# Digital_Output_CPU.net
KiCad netlist of a schematic drawn in Altium Designer
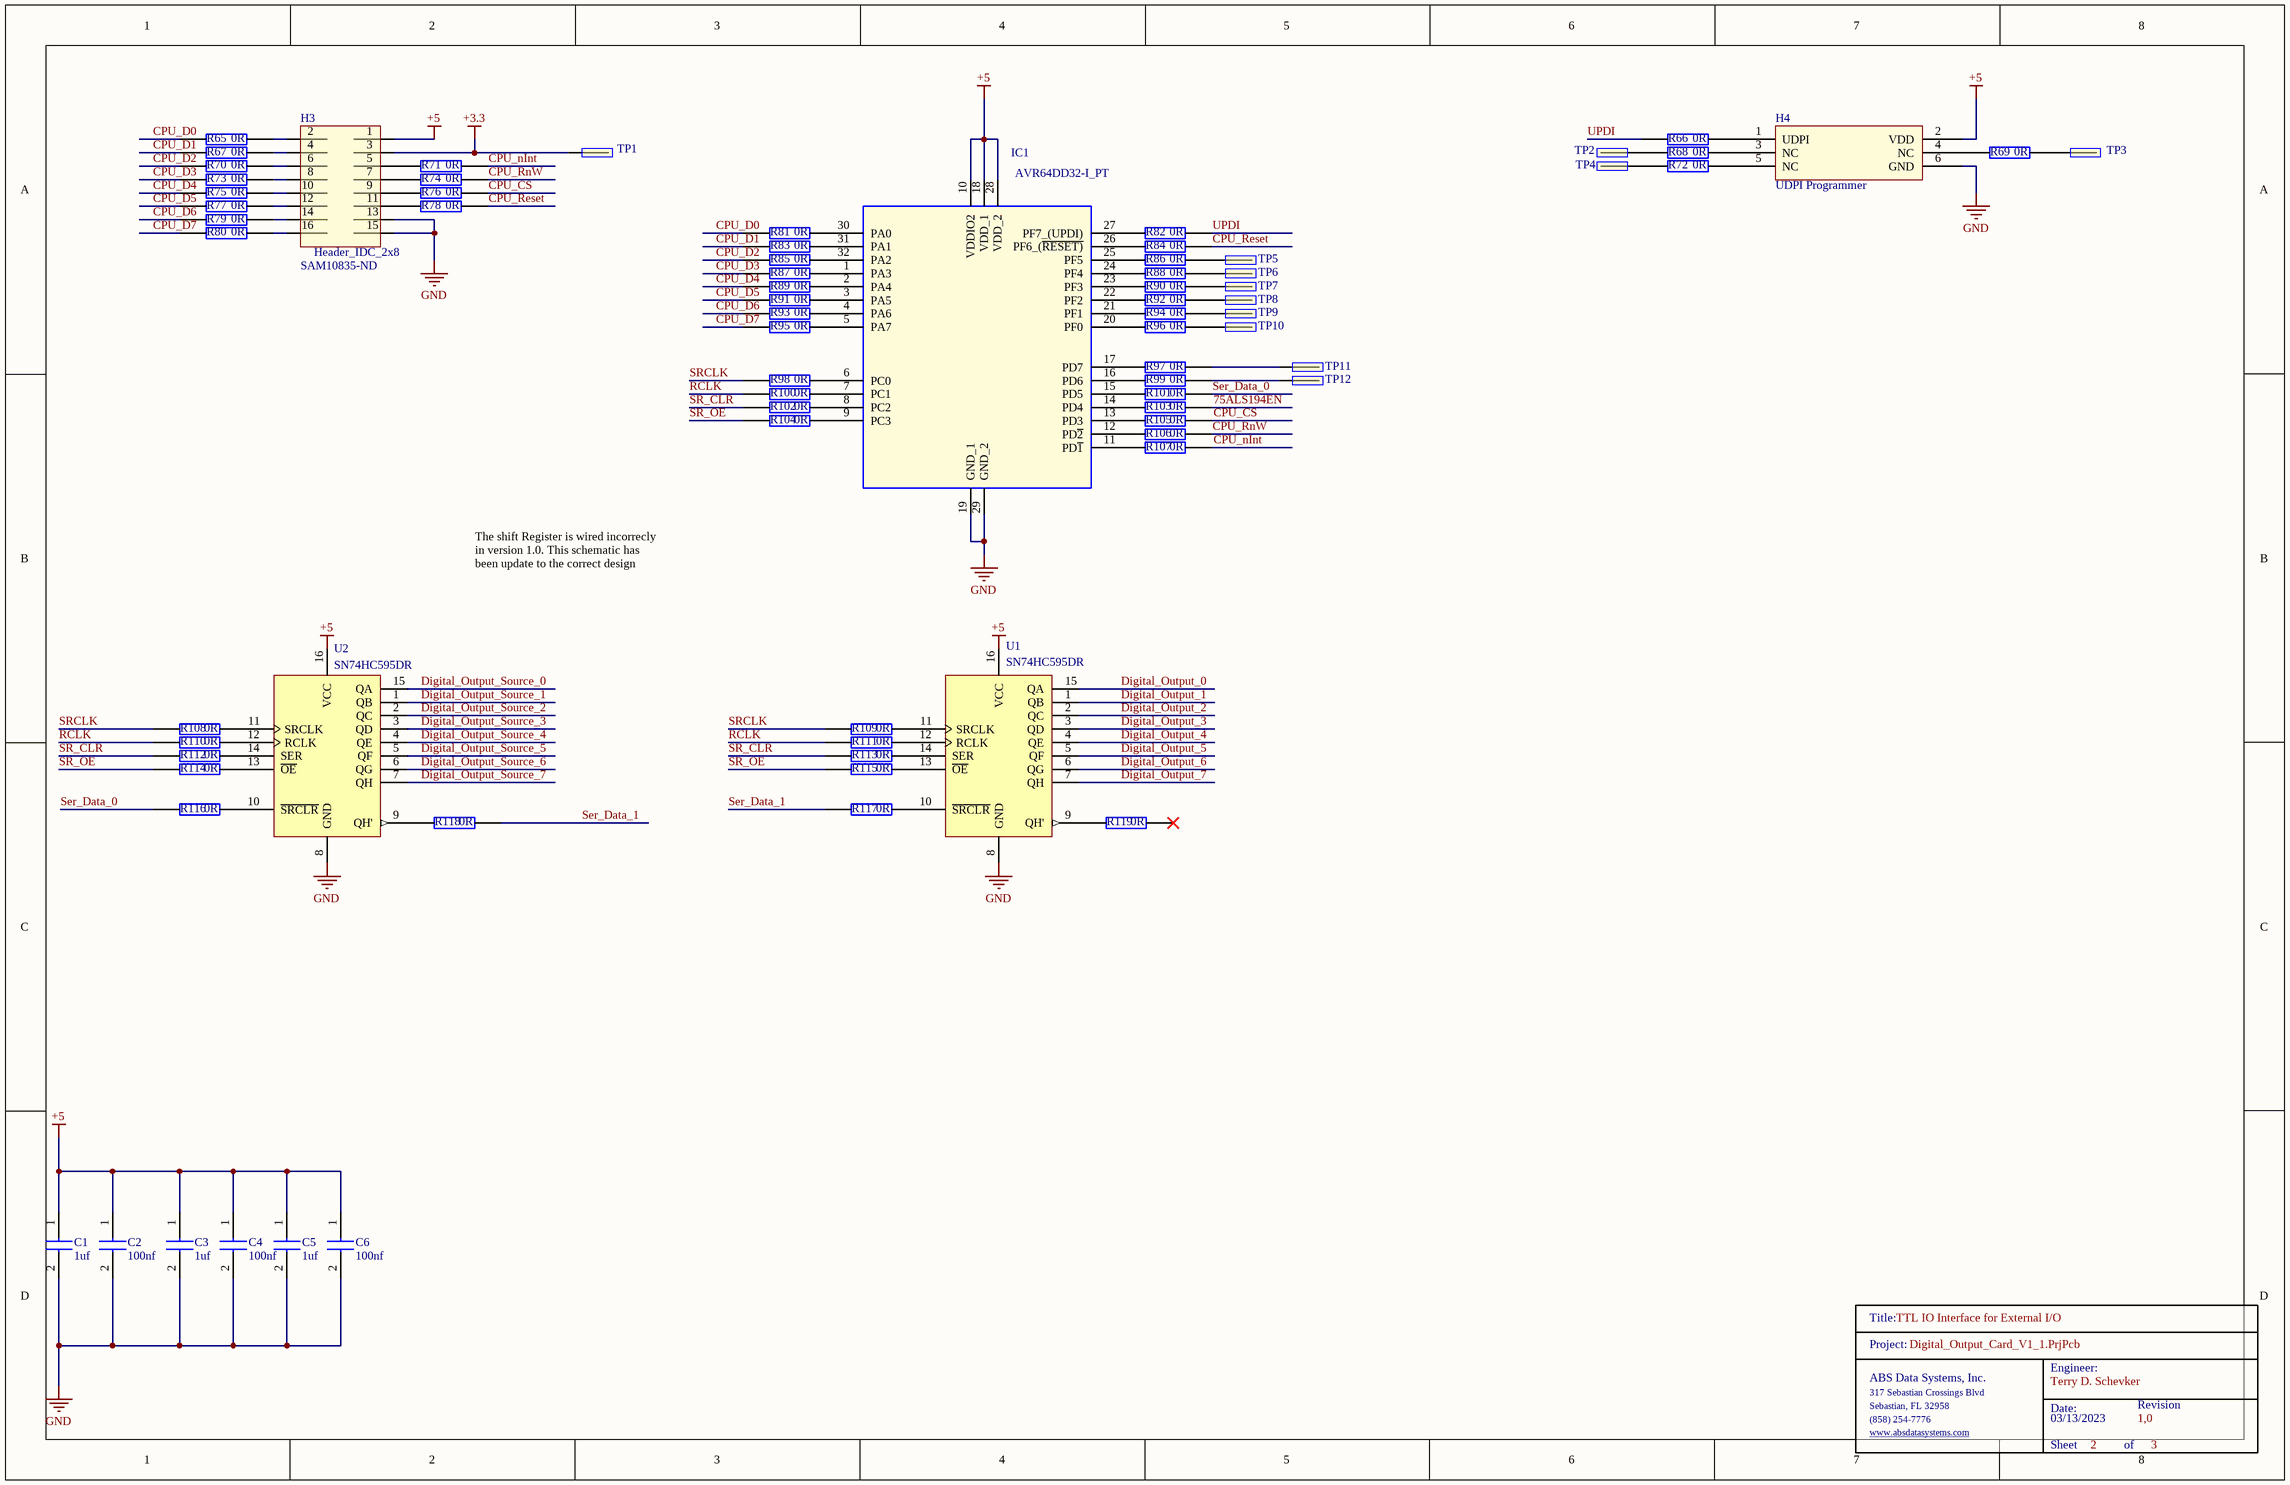
[diagram p0: Digital_Output_CPU.SchDoc]

(export (version "E")
  (design (tool "Eeschema 10.0.6"))
  (components
    (comp (ref "C1")
      (value "1uf")
      (footprint "0603")
      (description "Samsung Electro-Mechanics 0603 1uf")
      (libsource (lib "Capacitors") (part "CL10B105KA8NNNL"))
    )
    (comp (ref "C2")
      (value "100nf")
      (footprint "0603")
      (description "Samsung Electro-Mechanics 0603 100nf")
      (libsource (lib "Capacitors") (part "CL10B104JB8NNNC"))
    )
    (comp (ref "C3")
      (value "1uf")
      (footprint "0603")
      (description "Samsung Electro-Mechanics 0603 1uf")
      (libsource (lib "Capacitors") (part "CL10B105KA8NNNL"))
    )
    (comp (ref "C4")
      (value "100nf")
      (footprint "0603")
      (description "Samsung Electro-Mechanics 0603 100nf")
      (libsource (lib "Capacitors") (part "CL10B104JB8NNNC"))
    )
    (comp (ref "C5")
      (value "1uf")
      (footprint "0603")
      (description "Samsung Electro-Mechanics 0603 1uf")
      (libsource (lib "Capacitors") (part "CL10B105KA8NNNL"))
    )
    (comp (ref "C6")
      (value "100nf")
      (footprint "0603")
      (description "Samsung Electro-Mechanics 0603 100nf")
      (libsource (lib "Capacitors") (part "CL10B104JB8NNNC"))
    )
    (comp (ref "H3")
      (value "Header_IDC_2x8")
      (footprint "HEADER16")
      (description "16 Pin 2x8 Through Hold IDC Connector")
      (fields
        (field (name "MANUFACTURER") "Samtec")
        (field (name "MANUFACTURER PART NUMBER") "TST-108-01-G-D")
        (field (name "SUPPLIER PART NUMBER 1") "SAM10835-ND")
      )
      (libsource (lib "Misc") (part "Header_IDC_2x8"))
    )
    (comp (ref "H4")
      (value "UDPI Programmer")
      (footprint "HDR2X3")
      (description "6 Pin 2X3 Through Hole Header")
      (libsource (lib "Misc") (part "UDPI Programmer"))
    )
    (comp (ref "IC1")
      (value "AVR64DD32-I_PT")
      (footprint "QFP80P900X900X120-32N")
      (description "Integrated Circuit")
      (fields (field (name "MANUFACTURER_PART_NUMBER") "AVR64DD32-I/PT ¦ MULTI-VOLTAGE I/O"))
      (libsource (lib "CPU_Memory") (part "AVR64DD32-I_PT"))
    )
    (comp (ref "R65")
      (value "0R")
      (footprint "0603")
      (description "YAGEO 0603 0 ohm")
      (fields
        (field (name "MOUSER PART NUMBER") "603-RC0603JR-070RL")
        (field (name "MANUFACTURER_PART_NUMBER") "RC0603JR-070RL")
      )
      (libsource (lib "Resistors") (part "RC0603JR-070RL"))
    )
    (comp (ref "R66")
      (value "0R")
      (footprint "0603")
      (description "YAGEO 0603 0 ohm")
      (fields
        (field (name "MOUSER PART NUMBER") "603-RC0603JR-070RL")
        (field (name "MANUFACTURER_PART_NUMBER") "RC0603JR-070RL")
      )
      (libsource (lib "Resistors") (part "RC0603JR-070RL"))
    )
    (comp (ref "R67")
      (value "0R")
      (footprint "0603")
      (description "YAGEO 0603 0 ohm")
      (fields
        (field (name "MOUSER PART NUMBER") "603-RC0603JR-070RL")
        (field (name "MANUFACTURER_PART_NUMBER") "RC0603JR-070RL")
      )
      (libsource (lib "Resistors") (part "RC0603JR-070RL"))
    )
    (comp (ref "R68")
      (value "0R")
      (footprint "0603")
      (description "YAGEO 0603 0 ohm")
      (fields
        (field (name "MOUSER PART NUMBER") "603-RC0603JR-070RL")
        (field (name "MANUFACTURER_PART_NUMBER") "RC0603JR-070RL")
      )
      (libsource (lib "Resistors") (part "RC0603JR-070RL"))
    )
    (comp (ref "R69")
      (value "0R")
      (footprint "0603")
      (description "YAGEO 0603 0 ohm")
      (fields
        (field (name "MOUSER PART NUMBER") "603-RC0603JR-070RL")
        (field (name "MANUFACTURER_PART_NUMBER") "RC0603JR-070RL")
      )
      (libsource (lib "Resistors") (part "RC0603JR-070RL"))
    )
    (comp (ref "R70")
      (value "0R")
      (footprint "0603")
      (description "YAGEO 0603 0 ohm")
      (fields
        (field (name "MOUSER PART NUMBER") "603-RC0603JR-070RL")
        (field (name "MANUFACTURER_PART_NUMBER") "RC0603JR-070RL")
      )
      (libsource (lib "Resistors") (part "RC0603JR-070RL"))
    )
    (comp (ref "R71")
      (value "0R")
      (footprint "0603")
      (description "YAGEO 0603 0 ohm")
      (fields
        (field (name "MOUSER PART NUMBER") "603-RC0603JR-070RL")
        (field (name "MANUFACTURER_PART_NUMBER") "RC0603JR-070RL")
      )
      (libsource (lib "Resistors") (part "RC0603JR-070RL"))
    )
    (comp (ref "R72")
      (value "0R")
      (footprint "0603")
      (description "YAGEO 0603 0 ohm")
      (fields
        (field (name "MOUSER PART NUMBER") "603-RC0603JR-070RL")
        (field (name "MANUFACTURER_PART_NUMBER") "RC0603JR-070RL")
      )
      (libsource (lib "Resistors") (part "RC0603JR-070RL"))
    )
    (comp (ref "R73")
      (value "0R")
      (footprint "0603")
      (description "YAGEO 0603 0 ohm")
      (fields
        (field (name "MOUSER PART NUMBER") "603-RC0603JR-070RL")
        (field (name "MANUFACTURER_PART_NUMBER") "RC0603JR-070RL")
      )
      (libsource (lib "Resistors") (part "RC0603JR-070RL"))
    )
    (comp (ref "R74")
      (value "0R")
      (footprint "0603")
      (description "YAGEO 0603 0 ohm")
      (fields
        (field (name "MOUSER PART NUMBER") "603-RC0603JR-070RL")
        (field (name "MANUFACTURER_PART_NUMBER") "RC0603JR-070RL")
      )
      (libsource (lib "Resistors") (part "RC0603JR-070RL"))
    )
    (comp (ref "R75")
      (value "0R")
      (footprint "0603")
      (description "YAGEO 0603 0 ohm")
      (fields
        (field (name "MOUSER PART NUMBER") "603-RC0603JR-070RL")
        (field (name "MANUFACTURER_PART_NUMBER") "RC0603JR-070RL")
      )
      (libsource (lib "Resistors") (part "RC0603JR-070RL"))
    )
    (comp (ref "R76")
      (value "0R")
      (footprint "0603")
      (description "YAGEO 0603 0 ohm")
      (fields
        (field (name "MOUSER PART NUMBER") "603-RC0603JR-070RL")
        (field (name "MANUFACTURER_PART_NUMBER") "RC0603JR-070RL")
      )
      (libsource (lib "Resistors") (part "RC0603JR-070RL"))
    )
    (comp (ref "R77")
      (value "0R")
      (footprint "0603")
      (description "YAGEO 0603 0 ohm")
      (fields
        (field (name "MOUSER PART NUMBER") "603-RC0603JR-070RL")
        (field (name "MANUFACTURER_PART_NUMBER") "RC0603JR-070RL")
      )
      (libsource (lib "Resistors") (part "RC0603JR-070RL"))
    )
    (comp (ref "R78")
      (value "0R")
      (footprint "0603")
      (description "YAGEO 0603 0 ohm")
      (fields
        (field (name "MOUSER PART NUMBER") "603-RC0603JR-070RL")
        (field (name "MANUFACTURER_PART_NUMBER") "RC0603JR-070RL")
      )
      (libsource (lib "Resistors") (part "RC0603JR-070RL"))
    )
    (comp (ref "R79")
      (value "0R")
      (footprint "0603")
      (description "YAGEO 0603 0 ohm")
      (fields
        (field (name "MOUSER PART NUMBER") "603-RC0603JR-070RL")
        (field (name "MANUFACTURER_PART_NUMBER") "RC0603JR-070RL")
      )
      (libsource (lib "Resistors") (part "RC0603JR-070RL"))
    )
    (comp (ref "R80")
      (value "0R")
      (footprint "0603")
      (description "YAGEO 0603 0 ohm")
      (fields
        (field (name "MOUSER PART NUMBER") "603-RC0603JR-070RL")
        (field (name "MANUFACTURER_PART_NUMBER") "RC0603JR-070RL")
      )
      (libsource (lib "Resistors") (part "RC0603JR-070RL"))
    )
    (comp (ref "R81")
      (value "0R")
      (footprint "0603")
      (description "YAGEO 0603 0 ohm")
      (fields
        (field (name "MOUSER PART NUMBER") "603-RC0603JR-070RL")
        (field (name "MANUFACTURER_PART_NUMBER") "RC0603JR-070RL")
      )
      (libsource (lib "Resistors") (part "RC0603JR-070RL"))
    )
    (comp (ref "R82")
      (value "0R")
      (footprint "0603")
      (description "YAGEO 0603 0 ohm")
      (fields
        (field (name "MOUSER PART NUMBER") "603-RC0603JR-070RL")
        (field (name "MANUFACTURER_PART_NUMBER") "RC0603JR-070RL")
      )
      (libsource (lib "Resistors") (part "RC0603JR-070RL"))
    )
    (comp (ref "R83")
      (value "0R")
      (footprint "0603")
      (description "YAGEO 0603 0 ohm")
      (fields
        (field (name "MOUSER PART NUMBER") "603-RC0603JR-070RL")
        (field (name "MANUFACTURER_PART_NUMBER") "RC0603JR-070RL")
      )
      (libsource (lib "Resistors") (part "RC0603JR-070RL"))
    )
    (comp (ref "R84")
      (value "0R")
      (footprint "0603")
      (description "YAGEO 0603 0 ohm")
      (fields
        (field (name "MOUSER PART NUMBER") "603-RC0603JR-070RL")
        (field (name "MANUFACTURER_PART_NUMBER") "RC0603JR-070RL")
      )
      (libsource (lib "Resistors") (part "RC0603JR-070RL"))
    )
    (comp (ref "R85")
      (value "0R")
      (footprint "0603")
      (description "YAGEO 0603 0 ohm")
      (fields
        (field (name "MOUSER PART NUMBER") "603-RC0603JR-070RL")
        (field (name "MANUFACTURER_PART_NUMBER") "RC0603JR-070RL")
      )
      (libsource (lib "Resistors") (part "RC0603JR-070RL"))
    )
    (comp (ref "R86")
      (value "0R")
      (footprint "0603")
      (description "YAGEO 0603 0 ohm")
      (fields
        (field (name "MOUSER PART NUMBER") "603-RC0603JR-070RL")
        (field (name "MANUFACTURER_PART_NUMBER") "RC0603JR-070RL")
      )
      (libsource (lib "Resistors") (part "RC0603JR-070RL"))
    )
    (comp (ref "R87")
      (value "0R")
      (footprint "0603")
      (description "YAGEO 0603 0 ohm")
      (fields
        (field (name "MOUSER PART NUMBER") "603-RC0603JR-070RL")
        (field (name "MANUFACTURER_PART_NUMBER") "RC0603JR-070RL")
      )
      (libsource (lib "Resistors") (part "RC0603JR-070RL"))
    )
    (comp (ref "R88")
      (value "0R")
      (footprint "0603")
      (description "YAGEO 0603 0 ohm")
      (fields
        (field (name "MOUSER PART NUMBER") "603-RC0603JR-070RL")
        (field (name "MANUFACTURER_PART_NUMBER") "RC0603JR-070RL")
      )
      (libsource (lib "Resistors") (part "RC0603JR-070RL"))
    )
    (comp (ref "R89")
      (value "0R")
      (footprint "0603")
      (description "YAGEO 0603 0 ohm")
      (fields
        (field (name "MOUSER PART NUMBER") "603-RC0603JR-070RL")
        (field (name "MANUFACTURER_PART_NUMBER") "RC0603JR-070RL")
      )
      (libsource (lib "Resistors") (part "RC0603JR-070RL"))
    )
    (comp (ref "R90")
      (value "0R")
      (footprint "0603")
      (description "YAGEO 0603 0 ohm")
      (fields
        (field (name "MOUSER PART NUMBER") "603-RC0603JR-070RL")
        (field (name "MANUFACTURER_PART_NUMBER") "RC0603JR-070RL")
      )
      (libsource (lib "Resistors") (part "RC0603JR-070RL"))
    )
    (comp (ref "R91")
      (value "0R")
      (footprint "0603")
      (description "YAGEO 0603 0 ohm")
      (fields
        (field (name "MOUSER PART NUMBER") "603-RC0603JR-070RL")
        (field (name "MANUFACTURER_PART_NUMBER") "RC0603JR-070RL")
      )
      (libsource (lib "Resistors") (part "RC0603JR-070RL"))
    )
    (comp (ref "R92")
      (value "0R")
      (footprint "0603")
      (description "YAGEO 0603 0 ohm")
      (fields
        (field (name "MOUSER PART NUMBER") "603-RC0603JR-070RL")
        (field (name "MANUFACTURER_PART_NUMBER") "RC0603JR-070RL")
      )
      (libsource (lib "Resistors") (part "RC0603JR-070RL"))
    )
    (comp (ref "R93")
      (value "0R")
      (footprint "0603")
      (description "YAGEO 0603 0 ohm")
      (fields
        (field (name "MOUSER PART NUMBER") "603-RC0603JR-070RL")
        (field (name "MANUFACTURER_PART_NUMBER") "RC0603JR-070RL")
      )
      (libsource (lib "Resistors") (part "RC0603JR-070RL"))
    )
    (comp (ref "R94")
      (value "0R")
      (footprint "0603")
      (description "YAGEO 0603 0 ohm")
      (fields
        (field (name "MOUSER PART NUMBER") "603-RC0603JR-070RL")
        (field (name "MANUFACTURER_PART_NUMBER") "RC0603JR-070RL")
      )
      (libsource (lib "Resistors") (part "RC0603JR-070RL"))
    )
    (comp (ref "R95")
      (value "0R")
      (footprint "0603")
      (description "YAGEO 0603 0 ohm")
      (fields
        (field (name "MOUSER PART NUMBER") "603-RC0603JR-070RL")
        (field (name "MANUFACTURER_PART_NUMBER") "RC0603JR-070RL")
      )
      (libsource (lib "Resistors") (part "RC0603JR-070RL"))
    )
    (comp (ref "R96")
      (value "0R")
      (footprint "0603")
      (description "YAGEO 0603 0 ohm")
      (fields
        (field (name "MOUSER PART NUMBER") "603-RC0603JR-070RL")
        (field (name "MANUFACTURER_PART_NUMBER") "RC0603JR-070RL")
      )
      (libsource (lib "Resistors") (part "RC0603JR-070RL"))
    )
    (comp (ref "R97")
      (value "0R")
      (footprint "0603")
      (description "YAGEO 0603 0 ohm")
      (fields
        (field (name "MOUSER PART NUMBER") "603-RC0603JR-070RL")
        (field (name "MANUFACTURER_PART_NUMBER") "RC0603JR-070RL")
      )
      (libsource (lib "Resistors") (part "RC0603JR-070RL"))
    )
    (comp (ref "R98")
      (value "0R")
      (footprint "0603")
      (description "YAGEO 0603 0 ohm")
      (fields
        (field (name "MOUSER PART NUMBER") "603-RC0603JR-070RL")
        (field (name "MANUFACTURER_PART_NUMBER") "RC0603JR-070RL")
      )
      (libsource (lib "Resistors") (part "RC0603JR-070RL"))
    )
    (comp (ref "R99")
      (value "0R")
      (footprint "0603")
      (description "YAGEO 0603 0 ohm")
      (fields
        (field (name "MOUSER PART NUMBER") "603-RC0603JR-070RL")
        (field (name "MANUFACTURER_PART_NUMBER") "RC0603JR-070RL")
      )
      (libsource (lib "Resistors") (part "RC0603JR-070RL"))
    )
    (comp (ref "R100")
      (value "0R")
      (footprint "0603")
      (description "YAGEO 0603 0 ohm")
      (fields
        (field (name "MOUSER PART NUMBER") "603-RC0603JR-070RL")
        (field (name "MANUFACTURER_PART_NUMBER") "RC0603JR-070RL")
      )
      (libsource (lib "Resistors") (part "RC0603JR-070RL"))
    )
    (comp (ref "R101")
      (value "0R")
      (footprint "0603")
      (description "YAGEO 0603 0 ohm")
      (fields
        (field (name "MOUSER PART NUMBER") "603-RC0603JR-070RL")
        (field (name "MANUFACTURER_PART_NUMBER") "RC0603JR-070RL")
      )
      (libsource (lib "Resistors") (part "RC0603JR-070RL"))
    )
    (comp (ref "R102")
      (value "0R")
      (footprint "0603")
      (description "YAGEO 0603 0 ohm")
      (fields
        (field (name "MOUSER PART NUMBER") "603-RC0603JR-070RL")
        (field (name "MANUFACTURER_PART_NUMBER") "RC0603JR-070RL")
      )
      (libsource (lib "Resistors") (part "RC0603JR-070RL"))
    )
    (comp (ref "R103")
      (value "0R")
      (footprint "0603")
      (description "YAGEO 0603 0 ohm")
      (fields
        (field (name "MOUSER PART NUMBER") "603-RC0603JR-070RL")
        (field (name "MANUFACTURER_PART_NUMBER") "RC0603JR-070RL")
      )
      (libsource (lib "Resistors") (part "RC0603JR-070RL"))
    )
    (comp (ref "R104")
      (value "0R")
      (footprint "0603")
      (description "YAGEO 0603 0 ohm")
      (fields
        (field (name "MOUSER PART NUMBER") "603-RC0603JR-070RL")
        (field (name "MANUFACTURER_PART_NUMBER") "RC0603JR-070RL")
      )
      (libsource (lib "Resistors") (part "RC0603JR-070RL"))
    )
    (comp (ref "R105")
      (value "0R")
      (footprint "0603")
      (description "YAGEO 0603 0 ohm")
      (fields
        (field (name "MOUSER PART NUMBER") "603-RC0603JR-070RL")
        (field (name "MANUFACTURER_PART_NUMBER") "RC0603JR-070RL")
      )
      (libsource (lib "Resistors") (part "RC0603JR-070RL"))
    )
    (comp (ref "R106")
      (value "0R")
      (footprint "0603")
      (description "YAGEO 0603 0 ohm")
      (fields
        (field (name "MOUSER PART NUMBER") "603-RC0603JR-070RL")
        (field (name "MANUFACTURER_PART_NUMBER") "RC0603JR-070RL")
      )
      (libsource (lib "Resistors") (part "RC0603JR-070RL"))
    )
    (comp (ref "R107")
      (value "0R")
      (footprint "0603")
      (description "YAGEO 0603 0 ohm")
      (fields
        (field (name "MOUSER PART NUMBER") "603-RC0603JR-070RL")
        (field (name "MANUFACTURER_PART_NUMBER") "RC0603JR-070RL")
      )
      (libsource (lib "Resistors") (part "RC0603JR-070RL"))
    )
    (comp (ref "R108")
      (value "0R")
      (footprint "0603")
      (description "YAGEO 0603 0 ohm")
      (fields
        (field (name "MOUSER PART NUMBER") "603-RC0603JR-070RL")
        (field (name "MANUFACTURER_PART_NUMBER") "RC0603JR-070RL")
      )
      (libsource (lib "Resistors") (part "RC0603JR-070RL"))
    )
    (comp (ref "R109")
      (value "0R")
      (footprint "0603")
      (description "YAGEO 0603 0 ohm")
      (fields
        (field (name "MOUSER PART NUMBER") "603-RC0603JR-070RL")
        (field (name "MANUFACTURER_PART_NUMBER") "RC0603JR-070RL")
      )
      (libsource (lib "Resistors") (part "RC0603JR-070RL"))
    )
    (comp (ref "R110")
      (value "0R")
      (footprint "0603")
      (description "YAGEO 0603 0 ohm")
      (fields
        (field (name "MOUSER PART NUMBER") "603-RC0603JR-070RL")
        (field (name "MANUFACTURER_PART_NUMBER") "RC0603JR-070RL")
      )
      (libsource (lib "Resistors") (part "RC0603JR-070RL"))
    )
    (comp (ref "R111")
      (value "0R")
      (footprint "0603")
      (description "YAGEO 0603 0 ohm")
      (fields
        (field (name "MOUSER PART NUMBER") "603-RC0603JR-070RL")
        (field (name "MANUFACTURER_PART_NUMBER") "RC0603JR-070RL")
      )
      (libsource (lib "Resistors") (part "RC0603JR-070RL"))
    )
    (comp (ref "R112")
      (value "0R")
      (footprint "0603")
      (description "YAGEO 0603 0 ohm")
      (fields
        (field (name "MOUSER PART NUMBER") "603-RC0603JR-070RL")
        (field (name "MANUFACTURER_PART_NUMBER") "RC0603JR-070RL")
      )
      (libsource (lib "Resistors") (part "RC0603JR-070RL"))
    )
    (comp (ref "R113")
      (value "0R")
      (footprint "0603")
      (description "YAGEO 0603 0 ohm")
      (fields
        (field (name "MOUSER PART NUMBER") "603-RC0603JR-070RL")
        (field (name "MANUFACTURER_PART_NUMBER") "RC0603JR-070RL")
      )
      (libsource (lib "Resistors") (part "RC0603JR-070RL"))
    )
    (comp (ref "R114")
      (value "0R")
      (footprint "0603")
      (description "YAGEO 0603 0 ohm")
      (fields
        (field (name "MOUSER PART NUMBER") "603-RC0603JR-070RL")
        (field (name "MANUFACTURER_PART_NUMBER") "RC0603JR-070RL")
      )
      (libsource (lib "Resistors") (part "RC0603JR-070RL"))
    )
    (comp (ref "R115")
      (value "0R")
      (footprint "0603")
      (description "YAGEO 0603 0 ohm")
      (fields
        (field (name "MOUSER PART NUMBER") "603-RC0603JR-070RL")
        (field (name "MANUFACTURER_PART_NUMBER") "RC0603JR-070RL")
      )
      (libsource (lib "Resistors") (part "RC0603JR-070RL"))
    )
    (comp (ref "R116")
      (value "0R")
      (footprint "0603")
      (description "YAGEO 0603 0 ohm")
      (fields
        (field (name "MOUSER PART NUMBER") "603-RC0603JR-070RL")
        (field (name "MANUFACTURER_PART_NUMBER") "RC0603JR-070RL")
      )
      (libsource (lib "Resistors") (part "RC0603JR-070RL"))
    )
    (comp (ref "R117")
      (value "0R")
      (footprint "0603")
      (description "YAGEO 0603 0 ohm")
      (fields
        (field (name "MOUSER PART NUMBER") "603-RC0603JR-070RL")
        (field (name "MANUFACTURER_PART_NUMBER") "RC0603JR-070RL")
      )
      (libsource (lib "Resistors") (part "RC0603JR-070RL"))
    )
    (comp (ref "R118")
      (value "0R")
      (footprint "0603")
      (description "YAGEO 0603 0 ohm")
      (fields
        (field (name "MOUSER PART NUMBER") "603-RC0603JR-070RL")
        (field (name "MANUFACTURER_PART_NUMBER") "RC0603JR-070RL")
      )
      (libsource (lib "Resistors") (part "RC0603JR-070RL"))
    )
    (comp (ref "R119")
      (value "0R")
      (footprint "0603")
      (description "YAGEO 0603 0 ohm")
      (fields
        (field (name "MOUSER PART NUMBER") "603-RC0603JR-070RL")
        (field (name "MANUFACTURER_PART_NUMBER") "RC0603JR-070RL")
      )
      (libsource (lib "Resistors") (part "RC0603JR-070RL"))
    )
    (comp (ref "TitleBlock_1") (value "TitleBlock") (libsource (lib "Misc") (part "TitleBlock")))
    (comp (ref "TP1")
      (value "TP")
      (footprint "TP")
      (fields
        (field (name "MANUFACTURER") "Samtec")
        (field (name "MANUFACTURER PART NUMBER") "TST-105-01-G-D")
      )
      (libsource (lib "") (part "TP_1"))
    )
    (comp (ref "TP2")
      (value "TP")
      (footprint "TP")
      (fields
        (field (name "MANUFACTURER") "Samtec")
        (field (name "MANUFACTURER PART NUMBER") "TST-105-01-G-D")
      )
      (libsource (lib "Misc") (part "TP"))
    )
    (comp (ref "TP3")
      (value "TP")
      (footprint "TP")
      (fields
        (field (name "MANUFACTURER") "Samtec")
        (field (name "MANUFACTURER PART NUMBER") "TST-105-01-G-D")
      )
      (libsource (lib "") (part "TP_1"))
    )
    (comp (ref "TP4")
      (value "TP")
      (footprint "TP")
      (fields
        (field (name "MANUFACTURER") "Samtec")
        (field (name "MANUFACTURER PART NUMBER") "TST-105-01-G-D")
      )
      (libsource (lib "Misc") (part "TP"))
    )
    (comp (ref "TP5")
      (value "TP")
      (footprint "TP")
      (fields
        (field (name "MANUFACTURER") "Samtec")
        (field (name "MANUFACTURER PART NUMBER") "TST-105-01-G-D")
      )
      (libsource (lib "") (part "TP_1"))
    )
    (comp (ref "TP6")
      (value "TP")
      (footprint "TP")
      (fields
        (field (name "MANUFACTURER") "Samtec")
        (field (name "MANUFACTURER PART NUMBER") "TST-105-01-G-D")
      )
      (libsource (lib "") (part "TP_1"))
    )
    (comp (ref "TP7")
      (value "TP")
      (footprint "TP")
      (fields
        (field (name "MANUFACTURER") "Samtec")
        (field (name "MANUFACTURER PART NUMBER") "TST-105-01-G-D")
      )
      (libsource (lib "") (part "TP_1"))
    )
    (comp (ref "TP8")
      (value "TP")
      (footprint "TP")
      (fields
        (field (name "MANUFACTURER") "Samtec")
        (field (name "MANUFACTURER PART NUMBER") "TST-105-01-G-D")
      )
      (libsource (lib "") (part "TP_1"))
    )
    (comp (ref "TP9")
      (value "TP")
      (footprint "TP")
      (fields
        (field (name "MANUFACTURER") "Samtec")
        (field (name "MANUFACTURER PART NUMBER") "TST-105-01-G-D")
      )
      (libsource (lib "") (part "TP_1"))
    )
    (comp (ref "TP10")
      (value "TP")
      (footprint "TP")
      (fields
        (field (name "MANUFACTURER") "Samtec")
        (field (name "MANUFACTURER PART NUMBER") "TST-105-01-G-D")
      )
      (libsource (lib "") (part "TP_1"))
    )
    (comp (ref "TP11")
      (value "TP")
      (footprint "TP")
      (fields
        (field (name "MANUFACTURER") "Samtec")
        (field (name "MANUFACTURER PART NUMBER") "TST-105-01-G-D")
      )
      (libsource (lib "") (part "TP_1"))
    )
    (comp (ref "TP12")
      (value "TP")
      (footprint "TP")
      (fields
        (field (name "MANUFACTURER") "Samtec")
        (field (name "MANUFACTURER PART NUMBER") "TST-105-01-G-D")
      )
      (libsource (lib "") (part "TP_1"))
    )
    (comp (ref "U1")
      (value "SN74HC595DR")
      (footprint "SOIC_16_Narrow")
      (description "8-Bit Shift Registers With 3-State Output Registers, D0016A, LARGE T&R")
      (fields
        (field (name "GENERIC PART NUMBER") "SN74HC595")
        (field (name "MANUFACTURER") "Texas Instruments")
      )
      (libsource (lib "Logic") (part "SN74HC595DR"))
    )
    (comp (ref "U2")
      (value "SN74HC595DR")
      (footprint "SOIC_16_Narrow")
      (description "8-Bit Shift Registers With 3-State Output Registers, D0016A, LARGE T&R")
      (fields
        (field (name "GENERIC PART NUMBER") "SN74HC595")
        (field (name "MANUFACTURER") "Texas Instruments")
      )
      (libsource (lib "Logic") (part "SN74HC595DR"))
    )
  )
  (nets
    (net (code "1") (name "+3.3") (class "Default")
      (node (ref "H3") (pin "3") (pinfunction "3_3") (pintype "passive"))
      (node (ref "TP1") (pin "1") (pinfunction "1_1") (pintype "passive"))
    )
    (net (code "2") (name "+5") (class "Default")
      (node (ref "C1") (pin "1") (pinfunction "1_1") (pintype "passive"))
      (node (ref "C2") (pin "1") (pinfunction "1_1") (pintype "passive"))
      (node (ref "C3") (pin "1") (pinfunction "1_1") (pintype "passive"))
      (node (ref "C4") (pin "1") (pinfunction "1_1") (pintype "passive"))
      (node (ref "C5") (pin "1") (pinfunction "1_1") (pintype "passive"))
      (node (ref "C6") (pin "1") (pinfunction "1_1") (pintype "passive"))
      (node (ref "H3") (pin "1") (pinfunction "1_1") (pintype "passive"))
      (node (ref "H4") (pin "2") (pinfunction "VDD_2") (pintype "passive"))
      (node (ref "IC1") (pin "10") (pinfunction "VDDIO2_10") (pintype "passive"))
      (node (ref "IC1") (pin "18") (pinfunction "VDD_1_18") (pintype "passive"))
      (node (ref "IC1") (pin "28") (pinfunction "VDD_2_28") (pintype "passive"))
      (node (ref "U1") (pin "16") (pinfunction "VCC_16") (pintype "power_in"))
      (node (ref "U2") (pin "16") (pinfunction "VCC_16") (pintype "power_in"))
    )
    (net (code "3") (name "/75ALS194EN") (class "Default")
      (node (ref "R103") (pin "2") (pinfunction "2_2") (pintype "passive"))
    )
    (net (code "4") (name "/CPU_CS") (class "Default")
      (node (ref "R105") (pin "2") (pinfunction "2_2") (pintype "passive"))
      (node (ref "R76") (pin "2") (pinfunction "2_2") (pintype "passive"))
    )
    (net (code "5") (name "/CPU_D0") (class "Default")
      (node (ref "R65") (pin "1") (pinfunction "1_1") (pintype "passive"))
      (node (ref "R81") (pin "1") (pinfunction "1_1") (pintype "passive"))
    )
    (net (code "6") (name "/CPU_D1") (class "Default")
      (node (ref "R67") (pin "1") (pinfunction "1_1") (pintype "passive"))
      (node (ref "R83") (pin "1") (pinfunction "1_1") (pintype "passive"))
    )
    (net (code "7") (name "/CPU_D2") (class "Default")
      (node (ref "R70") (pin "1") (pinfunction "1_1") (pintype "passive"))
      (node (ref "R85") (pin "1") (pinfunction "1_1") (pintype "passive"))
    )
    (net (code "8") (name "/CPU_D3") (class "Default")
      (node (ref "R73") (pin "1") (pinfunction "1_1") (pintype "passive"))
      (node (ref "R87") (pin "1") (pinfunction "1_1") (pintype "passive"))
    )
    (net (code "9") (name "/CPU_D4") (class "Default")
      (node (ref "R75") (pin "1") (pinfunction "1_1") (pintype "passive"))
      (node (ref "R89") (pin "1") (pinfunction "1_1") (pintype "passive"))
    )
    (net (code "10") (name "/CPU_D5") (class "Default")
      (node (ref "R77") (pin "1") (pinfunction "1_1") (pintype "passive"))
      (node (ref "R91") (pin "1") (pinfunction "1_1") (pintype "passive"))
    )
    (net (code "11") (name "/CPU_D6") (class "Default")
      (node (ref "R79") (pin "1") (pinfunction "1_1") (pintype "passive"))
      (node (ref "R93") (pin "1") (pinfunction "1_1") (pintype "passive"))
    )
    (net (code "12") (name "/CPU_D7") (class "Default")
      (node (ref "R80") (pin "1") (pinfunction "1_1") (pintype "passive"))
      (node (ref "R95") (pin "1") (pinfunction "1_1") (pintype "passive"))
    )
    (net (code "13") (name "/CPU_Reset") (class "Default")
      (node (ref "R78") (pin "2") (pinfunction "2_2") (pintype "passive"))
      (node (ref "R84") (pin "2") (pinfunction "2_2") (pintype "passive"))
    )
    (net (code "14") (name "/CPU_RnW") (class "Default")
      (node (ref "R106") (pin "2") (pinfunction "2_2") (pintype "passive"))
      (node (ref "R74") (pin "2") (pinfunction "2_2") (pintype "passive"))
    )
    (net (code "15") (name "/CPU_nInt") (class "Default")
      (node (ref "R107") (pin "2") (pinfunction "2_2") (pintype "passive"))
      (node (ref "R71") (pin "2") (pinfunction "2_2") (pintype "passive"))
    )
    (net (code "16") (name "/Digital_Output_0") (class "Default")
      (node (ref "U1") (pin "15") (pinfunction "QA_15") (pintype "tri_state"))
    )
    (net (code "17") (name "/Digital_Output_1") (class "Default")
      (node (ref "U1") (pin "1") (pinfunction "QB_1") (pintype "tri_state"))
    )
    (net (code "18") (name "/Digital_Output_2") (class "Default")
      (node (ref "U1") (pin "2") (pinfunction "QC_2") (pintype "tri_state"))
    )
    (net (code "19") (name "/Digital_Output_3") (class "Default")
      (node (ref "U1") (pin "3") (pinfunction "QD_3") (pintype "tri_state"))
    )
    (net (code "20") (name "/Digital_Output_4") (class "Default")
      (node (ref "U1") (pin "4") (pinfunction "QE_4") (pintype "tri_state"))
    )
    (net (code "21") (name "/Digital_Output_5") (class "Default")
      (node (ref "U1") (pin "5") (pinfunction "QF_5") (pintype "tri_state"))
    )
    (net (code "22") (name "/Digital_Output_6") (class "Default")
      (node (ref "U1") (pin "6") (pinfunction "QG_6") (pintype "tri_state"))
    )
    (net (code "23") (name "/Digital_Output_7") (class "Default")
      (node (ref "U1") (pin "7") (pinfunction "QH_7") (pintype "tri_state"))
    )
    (net (code "24") (name "/Digital_Output_Source_0") (class "Default")
      (node (ref "U2") (pin "15") (pinfunction "QA_15") (pintype "tri_state"))
    )
    (net (code "25") (name "/Digital_Output_Source_1") (class "Default")
      (node (ref "U2") (pin "1") (pinfunction "QB_1") (pintype "tri_state"))
    )
    (net (code "26") (name "/Digital_Output_Source_2") (class "Default")
      (node (ref "U2") (pin "2") (pinfunction "QC_2") (pintype "tri_state"))
    )
    (net (code "27") (name "/Digital_Output_Source_3") (class "Default")
      (node (ref "U2") (pin "3") (pinfunction "QD_3") (pintype "tri_state"))
    )
    (net (code "28") (name "/Digital_Output_Source_4") (class "Default")
      (node (ref "U2") (pin "4") (pinfunction "QE_4") (pintype "tri_state"))
    )
    (net (code "29") (name "/Digital_Output_Source_5") (class "Default")
      (node (ref "U2") (pin "5") (pinfunction "QF_5") (pintype "tri_state"))
    )
    (net (code "30") (name "/Digital_Output_Source_6") (class "Default")
      (node (ref "U2") (pin "6") (pinfunction "QG_6") (pintype "tri_state"))
    )
    (net (code "31") (name "/Digital_Output_Source_7") (class "Default")
      (node (ref "U2") (pin "7") (pinfunction "QH_7") (pintype "tri_state"))
    )
    (net (code "32") (name "/RCLK") (class "Default")
      (node (ref "R100") (pin "1") (pinfunction "1_1") (pintype "passive"))
      (node (ref "R110") (pin "1") (pinfunction "1_1") (pintype "passive"))
      (node (ref "R111") (pin "1") (pinfunction "1_1") (pintype "passive"))
    )
    (net (code "33") (name "/SRCLK") (class "Default")
      (node (ref "R108") (pin "1") (pinfunction "1_1") (pintype "passive"))
      (node (ref "R109") (pin "1") (pinfunction "1_1") (pintype "passive"))
      (node (ref "R98") (pin "1") (pinfunction "1_1") (pintype "passive"))
    )
    (net (code "34") (name "/SR_CLR") (class "Default")
      (node (ref "R102") (pin "1") (pinfunction "1_1") (pintype "passive"))
      (node (ref "R112") (pin "1") (pinfunction "1_1") (pintype "passive"))
      (node (ref "R113") (pin "1") (pinfunction "1_1") (pintype "passive"))
    )
    (net (code "35") (name "/SR_OE") (class "Default")
      (node (ref "R104") (pin "1") (pinfunction "1_1") (pintype "passive"))
      (node (ref "R114") (pin "1") (pinfunction "1_1") (pintype "passive"))
      (node (ref "R115") (pin "1") (pinfunction "1_1") (pintype "passive"))
    )
    (net (code "36") (name "/Ser_Data_0") (class "Default")
      (node (ref "R101") (pin "2") (pinfunction "2_2") (pintype "passive"))
      (node (ref "R116") (pin "1") (pinfunction "1_1") (pintype "passive"))
    )
    (net (code "37") (name "/Ser_Data_1") (class "Default")
      (node (ref "R117") (pin "1") (pinfunction "1_1") (pintype "passive"))
      (node (ref "R118") (pin "2") (pinfunction "2_2") (pintype "passive"))
    )
    (net (code "38") (name "/UPDI") (class "Default")
      (node (ref "R66") (pin "1") (pinfunction "1_1") (pintype "passive"))
      (node (ref "R82") (pin "2") (pinfunction "2_2") (pintype "passive"))
    )
    (net (code "39") (name "GND") (class "Default")
      (node (ref "C1") (pin "2") (pinfunction "2_2") (pintype "passive"))
      (node (ref "C2") (pin "2") (pinfunction "2_2") (pintype "passive"))
      (node (ref "C3") (pin "2") (pinfunction "2_2") (pintype "passive"))
      (node (ref "C4") (pin "2") (pinfunction "2_2") (pintype "passive"))
      (node (ref "C5") (pin "2") (pinfunction "2_2") (pintype "passive"))
      (node (ref "C6") (pin "2") (pinfunction "2_2") (pintype "passive"))
      (node (ref "H3") (pin "13") (pinfunction "13_13") (pintype "passive"))
      (node (ref "H3") (pin "15") (pinfunction "15_15") (pintype "passive"))
      (node (ref "H4") (pin "6") (pinfunction "GND_6") (pintype "passive"))
      (node (ref "IC1") (pin "19") (pinfunction "GND_1_19") (pintype "passive"))
      (node (ref "IC1") (pin "29") (pinfunction "GND_2_29") (pintype "passive"))
      (node (ref "U1") (pin "8") (pinfunction "GND_8") (pintype "power_in"))
      (node (ref "U2") (pin "8") (pinfunction "GND_8") (pintype "power_in"))
    )
    (net (code "40") (name "Net-(H3-Pad2)") (class "Default")
      (node (ref "H3") (pin "2") (pinfunction "2_2") (pintype "passive"))
      (node (ref "R65") (pin "2") (pinfunction "2_2") (pintype "passive"))
    )
    (net (code "41") (name "Net-(H3-Pad4)") (class "Default")
      (node (ref "H3") (pin "4") (pinfunction "4_4") (pintype "passive"))
      (node (ref "R67") (pin "2") (pinfunction "2_2") (pintype "passive"))
    )
    (net (code "42") (name "Net-(H3-Pad5)") (class "Default")
      (node (ref "H3") (pin "5") (pinfunction "5_5") (pintype "passive"))
      (node (ref "R71") (pin "1") (pinfunction "1_1") (pintype "passive"))
    )
    (net (code "43") (name "Net-(H3-Pad6)") (class "Default")
      (node (ref "H3") (pin "6") (pinfunction "6_6") (pintype "passive"))
      (node (ref "R70") (pin "2") (pinfunction "2_2") (pintype "passive"))
    )
    (net (code "44") (name "Net-(H3-Pad7)") (class "Default")
      (node (ref "H3") (pin "7") (pinfunction "7_7") (pintype "passive"))
      (node (ref "R74") (pin "1") (pinfunction "1_1") (pintype "passive"))
    )
    (net (code "45") (name "Net-(H3-Pad8)") (class "Default")
      (node (ref "H3") (pin "8") (pinfunction "8_8") (pintype "passive"))
      (node (ref "R73") (pin "2") (pinfunction "2_2") (pintype "passive"))
    )
    (net (code "46") (name "Net-(H3-Pad9)") (class "Default")
      (node (ref "H3") (pin "9") (pinfunction "9_9") (pintype "passive"))
      (node (ref "R76") (pin "1") (pinfunction "1_1") (pintype "passive"))
    )
    (net (code "47") (name "Net-(H3-Pad10)") (class "Default")
      (node (ref "H3") (pin "10") (pinfunction "10_10") (pintype "passive"))
      (node (ref "R75") (pin "2") (pinfunction "2_2") (pintype "passive"))
    )
    (net (code "48") (name "Net-(H3-Pad11)") (class "Default")
      (node (ref "H3") (pin "11") (pinfunction "11_11") (pintype "passive"))
      (node (ref "R78") (pin "1") (pinfunction "1_1") (pintype "passive"))
    )
    (net (code "49") (name "Net-(H3-Pad12)") (class "Default")
      (node (ref "H3") (pin "12") (pinfunction "12_12") (pintype "passive"))
      (node (ref "R77") (pin "2") (pinfunction "2_2") (pintype "passive"))
    )
    (net (code "50") (name "Net-(H3-Pad14)") (class "Default")
      (node (ref "H3") (pin "14") (pinfunction "14_14") (pintype "passive"))
      (node (ref "R79") (pin "2") (pinfunction "2_2") (pintype "passive"))
    )
    (net (code "51") (name "Net-(H3-Pad16)") (class "Default")
      (node (ref "H3") (pin "16") (pinfunction "16_16") (pintype "passive"))
      (node (ref "R80") (pin "2") (pinfunction "2_2") (pintype "passive"))
    )
    (net (code "52") (name "Net-(H4-NC-Pad3)") (class "Default")
      (node (ref "H4") (pin "3") (pinfunction "NC_3") (pintype "passive"))
      (node (ref "R68") (pin "2") (pinfunction "2_2") (pintype "passive"))
    )
    (net (code "53") (name "Net-(H4-NC-Pad4)") (class "Default")
      (node (ref "H4") (pin "4") (pinfunction "NC_4") (pintype "passive"))
      (node (ref "R69") (pin "1") (pinfunction "1_1") (pintype "passive"))
    )
    (net (code "54") (name "Net-(H4-NC-Pad5)") (class "Default")
      (node (ref "H4") (pin "5") (pinfunction "NC_5") (pintype "passive"))
      (node (ref "R72") (pin "2") (pinfunction "2_2") (pintype "passive"))
    )
    (net (code "55") (name "Net-(H4-UDPI)") (class "Default")
      (node (ref "H4") (pin "1") (pinfunction "UDPI_1") (pintype "passive"))
      (node (ref "R66") (pin "2") (pinfunction "2_2") (pintype "passive"))
    )
    (net (code "56") (name "Net-(IC1-PA0)") (class "Default")
      (node (ref "IC1") (pin "30") (pinfunction "PA0_30") (pintype "passive"))
      (node (ref "R81") (pin "2") (pinfunction "2_2") (pintype "passive"))
    )
    (net (code "57") (name "Net-(IC1-PA1)") (class "Default")
      (node (ref "IC1") (pin "31") (pinfunction "PA1_31") (pintype "passive"))
      (node (ref "R83") (pin "2") (pinfunction "2_2") (pintype "passive"))
    )
    (net (code "58") (name "Net-(IC1-PA2)") (class "Default")
      (node (ref "IC1") (pin "32") (pinfunction "PA2_32") (pintype "passive"))
      (node (ref "R85") (pin "2") (pinfunction "2_2") (pintype "passive"))
    )
    (net (code "59") (name "Net-(IC1-PA3)") (class "Default")
      (node (ref "IC1") (pin "1") (pinfunction "PA3_1") (pintype "passive"))
      (node (ref "R87") (pin "2") (pinfunction "2_2") (pintype "passive"))
    )
    (net (code "60") (name "Net-(IC1-PA4)") (class "Default")
      (node (ref "IC1") (pin "2") (pinfunction "PA4_2") (pintype "passive"))
      (node (ref "R89") (pin "2") (pinfunction "2_2") (pintype "passive"))
    )
    (net (code "61") (name "Net-(IC1-PA5)") (class "Default")
      (node (ref "IC1") (pin "3") (pinfunction "PA5_3") (pintype "passive"))
      (node (ref "R91") (pin "2") (pinfunction "2_2") (pintype "passive"))
    )
    (net (code "62") (name "Net-(IC1-PA6)") (class "Default")
      (node (ref "IC1") (pin "4") (pinfunction "PA6_4") (pintype "passive"))
      (node (ref "R93") (pin "2") (pinfunction "2_2") (pintype "passive"))
    )
    (net (code "63") (name "Net-(IC1-PA7)") (class "Default")
      (node (ref "IC1") (pin "5") (pinfunction "PA7_5") (pintype "passive"))
      (node (ref "R95") (pin "2") (pinfunction "2_2") (pintype "passive"))
    )
    (net (code "64") (name "Net-(IC1-PC0)") (class "Default")
      (node (ref "IC1") (pin "6") (pinfunction "PC0_6") (pintype "passive"))
      (node (ref "R98") (pin "2") (pinfunction "2_2") (pintype "passive"))
    )
    (net (code "65") (name "Net-(IC1-PC1)") (class "Default")
      (node (ref "IC1") (pin "7") (pinfunction "PC1_7") (pintype "passive"))
      (node (ref "R100") (pin "2") (pinfunction "2_2") (pintype "passive"))
    )
    (net (code "66") (name "Net-(IC1-PC2)") (class "Default")
      (node (ref "IC1") (pin "8") (pinfunction "PC2_8") (pintype "passive"))
      (node (ref "R102") (pin "2") (pinfunction "2_2") (pintype "passive"))
    )
    (net (code "67") (name "Net-(IC1-PC3)") (class "Default")
      (node (ref "IC1") (pin "9") (pinfunction "PC3_9") (pintype "passive"))
      (node (ref "R104") (pin "2") (pinfunction "2_2") (pintype "passive"))
    )
    (net (code "68") (name "Net-(IC1-PD3)") (class "Default")
      (node (ref "IC1") (pin "13") (pinfunction "PD3_13") (pintype "passive"))
      (node (ref "R105") (pin "1") (pinfunction "1_1") (pintype "passive"))
    )
    (net (code "69") (name "Net-(IC1-PD4)") (class "Default")
      (node (ref "IC1") (pin "14") (pinfunction "PD4_14") (pintype "passive"))
      (node (ref "R103") (pin "1") (pinfunction "1_1") (pintype "passive"))
    )
    (net (code "70") (name "Net-(IC1-PD5)") (class "Default")
      (node (ref "IC1") (pin "15") (pinfunction "PD5_15") (pintype "passive"))
      (node (ref "R101") (pin "1") (pinfunction "1_1") (pintype "passive"))
    )
    (net (code "71") (name "Net-(IC1-PD6)") (class "Default")
      (node (ref "IC1") (pin "16") (pinfunction "PD6_16") (pintype "passive"))
      (node (ref "R99") (pin "1") (pinfunction "1_1") (pintype "passive"))
    )
    (net (code "72") (name "Net-(IC1-PD7)") (class "Default")
      (node (ref "IC1") (pin "17") (pinfunction "PD7_17") (pintype "passive"))
      (node (ref "R97") (pin "1") (pinfunction "1_1") (pintype "passive"))
    )
    (net (code "73") (name "Net-(IC1-PD~{1})") (class "Default")
      (node (ref "IC1") (pin "11") (pinfunction "PD~{1}_11") (pintype "passive"))
      (node (ref "R107") (pin "1") (pinfunction "1_1") (pintype "passive"))
    )
    (net (code "74") (name "Net-(IC1-PD~{2})") (class "Default")
      (node (ref "IC1") (pin "12") (pinfunction "PD~{2}_12") (pintype "passive"))
      (node (ref "R106") (pin "1") (pinfunction "1_1") (pintype "passive"))
    )
    (net (code "75") (name "Net-(IC1-PF0)") (class "Default")
      (node (ref "IC1") (pin "20") (pinfunction "PF0_20") (pintype "passive"))
      (node (ref "R96") (pin "1") (pinfunction "1_1") (pintype "passive"))
    )
    (net (code "76") (name "Net-(IC1-PF1)") (class "Default")
      (node (ref "IC1") (pin "21") (pinfunction "PF1_21") (pintype "passive"))
      (node (ref "R94") (pin "1") (pinfunction "1_1") (pintype "passive"))
    )
    (net (code "77") (name "Net-(IC1-PF2)") (class "Default")
      (node (ref "IC1") (pin "22") (pinfunction "PF2_22") (pintype "passive"))
      (node (ref "R92") (pin "1") (pinfunction "1_1") (pintype "passive"))
    )
    (net (code "78") (name "Net-(IC1-PF3)") (class "Default")
      (node (ref "IC1") (pin "23") (pinfunction "PF3_23") (pintype "passive"))
      (node (ref "R90") (pin "1") (pinfunction "1_1") (pintype "passive"))
    )
    (net (code "79") (name "Net-(IC1-PF4)") (class "Default")
      (node (ref "IC1") (pin "24") (pinfunction "PF4_24") (pintype "passive"))
      (node (ref "R88") (pin "1") (pinfunction "1_1") (pintype "passive"))
    )
    (net (code "80") (name "Net-(IC1-PF5)") (class "Default")
      (node (ref "IC1") (pin "25") (pinfunction "PF5_25") (pintype "passive"))
      (node (ref "R86") (pin "1") (pinfunction "1_1") (pintype "passive"))
    )
    (net (code "81") (name "Net-(IC1-PF6_(~{RESET)})") (class "Default")
      (node (ref "IC1") (pin "26") (pinfunction "PF6_(~{RESET)}_26") (pintype "passive"))
      (node (ref "R84") (pin "1") (pinfunction "1_1") (pintype "passive"))
    )
    (net (code "82") (name "Net-(IC1-PF7_(UPDI))") (class "Default")
      (node (ref "IC1") (pin "27") (pinfunction "PF7_(UPDI)_27") (pintype "passive"))
      (node (ref "R82") (pin "1") (pinfunction "1_1") (pintype "passive"))
    )
    (net (code "83") (name "Net-(R68-Pad1)") (class "Default")
      (node (ref "R68") (pin "1") (pinfunction "1_1") (pintype "passive"))
      (node (ref "TP2") (pin "1") (pinfunction "1_1") (pintype "passive"))
    )
    (net (code "84") (name "Net-(R69-Pad2)") (class "Default")
      (node (ref "R69") (pin "2") (pinfunction "2_2") (pintype "passive"))
      (node (ref "TP3") (pin "1") (pinfunction "1_1") (pintype "passive"))
    )
    (net (code "85") (name "Net-(R72-Pad1)") (class "Default")
      (node (ref "R72") (pin "1") (pinfunction "1_1") (pintype "passive"))
      (node (ref "TP4") (pin "1") (pinfunction "1_1") (pintype "passive"))
    )
    (net (code "86") (name "Net-(R86-Pad2)") (class "Default")
      (node (ref "R86") (pin "2") (pinfunction "2_2") (pintype "passive"))
      (node (ref "TP5") (pin "1") (pinfunction "1_1") (pintype "passive"))
    )
    (net (code "87") (name "Net-(R88-Pad2)") (class "Default")
      (node (ref "R88") (pin "2") (pinfunction "2_2") (pintype "passive"))
      (node (ref "TP6") (pin "1") (pinfunction "1_1") (pintype "passive"))
    )
    (net (code "88") (name "Net-(R90-Pad2)") (class "Default")
      (node (ref "R90") (pin "2") (pinfunction "2_2") (pintype "passive"))
      (node (ref "TP7") (pin "1") (pinfunction "1_1") (pintype "passive"))
    )
    (net (code "89") (name "Net-(R92-Pad2)") (class "Default")
      (node (ref "R92") (pin "2") (pinfunction "2_2") (pintype "passive"))
      (node (ref "TP8") (pin "1") (pinfunction "1_1") (pintype "passive"))
    )
    (net (code "90") (name "Net-(R94-Pad2)") (class "Default")
      (node (ref "R94") (pin "2") (pinfunction "2_2") (pintype "passive"))
      (node (ref "TP9") (pin "1") (pinfunction "1_1") (pintype "passive"))
    )
    (net (code "91") (name "Net-(R96-Pad2)") (class "Default")
      (node (ref "R96") (pin "2") (pinfunction "2_2") (pintype "passive"))
      (node (ref "TP10") (pin "1") (pinfunction "1_1") (pintype "passive"))
    )
    (net (code "92") (name "Net-(R97-Pad2)") (class "Default")
      (node (ref "R97") (pin "2") (pinfunction "2_2") (pintype "passive"))
      (node (ref "TP11") (pin "1") (pinfunction "1_1") (pintype "passive"))
    )
    (net (code "93") (name "Net-(R99-Pad2)") (class "Default")
      (node (ref "R99") (pin "2") (pinfunction "2_2") (pintype "passive"))
      (node (ref "TP12") (pin "1") (pinfunction "1_1") (pintype "passive"))
    )
    (net (code "94") (name "Net-(U1-QH')") (class "Default")
      (node (ref "R119") (pin "1") (pinfunction "1_1") (pintype "passive"))
      (node (ref "U1") (pin "9") (pinfunction "QH'_9") (pintype "output"))
    )
    (net (code "95") (name "Net-(U1-RCLK)") (class "Default")
      (node (ref "R111") (pin "2") (pinfunction "2_2") (pintype "passive"))
      (node (ref "U1") (pin "12") (pinfunction "RCLK_12") (pintype "passive"))
    )
    (net (code "96") (name "Net-(U1-SER)") (class "Default")
      (node (ref "R113") (pin "2") (pinfunction "2_2") (pintype "passive"))
      (node (ref "U1") (pin "14") (pinfunction "SER_14") (pintype "passive"))
    )
    (net (code "97") (name "Net-(U1-SRCLK)") (class "Default")
      (node (ref "R109") (pin "2") (pinfunction "2_2") (pintype "passive"))
      (node (ref "U1") (pin "11") (pinfunction "SRCLK_11") (pintype "passive"))
    )
    (net (code "98") (name "Net-(U1-~{OE})") (class "Default")
      (node (ref "R115") (pin "2") (pinfunction "2_2") (pintype "passive"))
      (node (ref "U1") (pin "13") (pinfunction "~{OE}_13") (pintype "passive"))
    )
    (net (code "99") (name "Net-(U1-~{SRCLR})") (class "Default")
      (node (ref "R117") (pin "2") (pinfunction "2_2") (pintype "passive"))
      (node (ref "U1") (pin "10") (pinfunction "~{SRCLR}_10") (pintype "passive"))
    )
    (net (code "100") (name "Net-(U2-QH')") (class "Default")
      (node (ref "R118") (pin "1") (pinfunction "1_1") (pintype "passive"))
      (node (ref "U2") (pin "9") (pinfunction "QH'_9") (pintype "output"))
    )
    (net (code "101") (name "Net-(U2-RCLK)") (class "Default")
      (node (ref "R110") (pin "2") (pinfunction "2_2") (pintype "passive"))
      (node (ref "U2") (pin "12") (pinfunction "RCLK_12") (pintype "passive"))
    )
    (net (code "102") (name "Net-(U2-SER)") (class "Default")
      (node (ref "R112") (pin "2") (pinfunction "2_2") (pintype "passive"))
      (node (ref "U2") (pin "14") (pinfunction "SER_14") (pintype "passive"))
    )
    (net (code "103") (name "Net-(U2-SRCLK)") (class "Default")
      (node (ref "R108") (pin "2") (pinfunction "2_2") (pintype "passive"))
      (node (ref "U2") (pin "11") (pinfunction "SRCLK_11") (pintype "passive"))
    )
    (net (code "104") (name "Net-(U2-~{OE})") (class "Default")
      (node (ref "R114") (pin "2") (pinfunction "2_2") (pintype "passive"))
      (node (ref "U2") (pin "13") (pinfunction "~{OE}_13") (pintype "passive"))
    )
    (net (code "105") (name "Net-(U2-~{SRCLR})") (class "Default")
      (node (ref "R116") (pin "2") (pinfunction "2_2") (pintype "passive"))
      (node (ref "U2") (pin "10") (pinfunction "~{SRCLR}_10") (pintype "passive"))
    )
    (net (code "106") (name "unconnected-(R119-Pad2)") (class "Default")
      (node (ref "R119") (pin "2") (pinfunction "2_2") (pintype "passive+no_connect"))
    )
  )
)
